# berlingo_synth.net
KiCad netlist of a schematic drawn in EAGLE
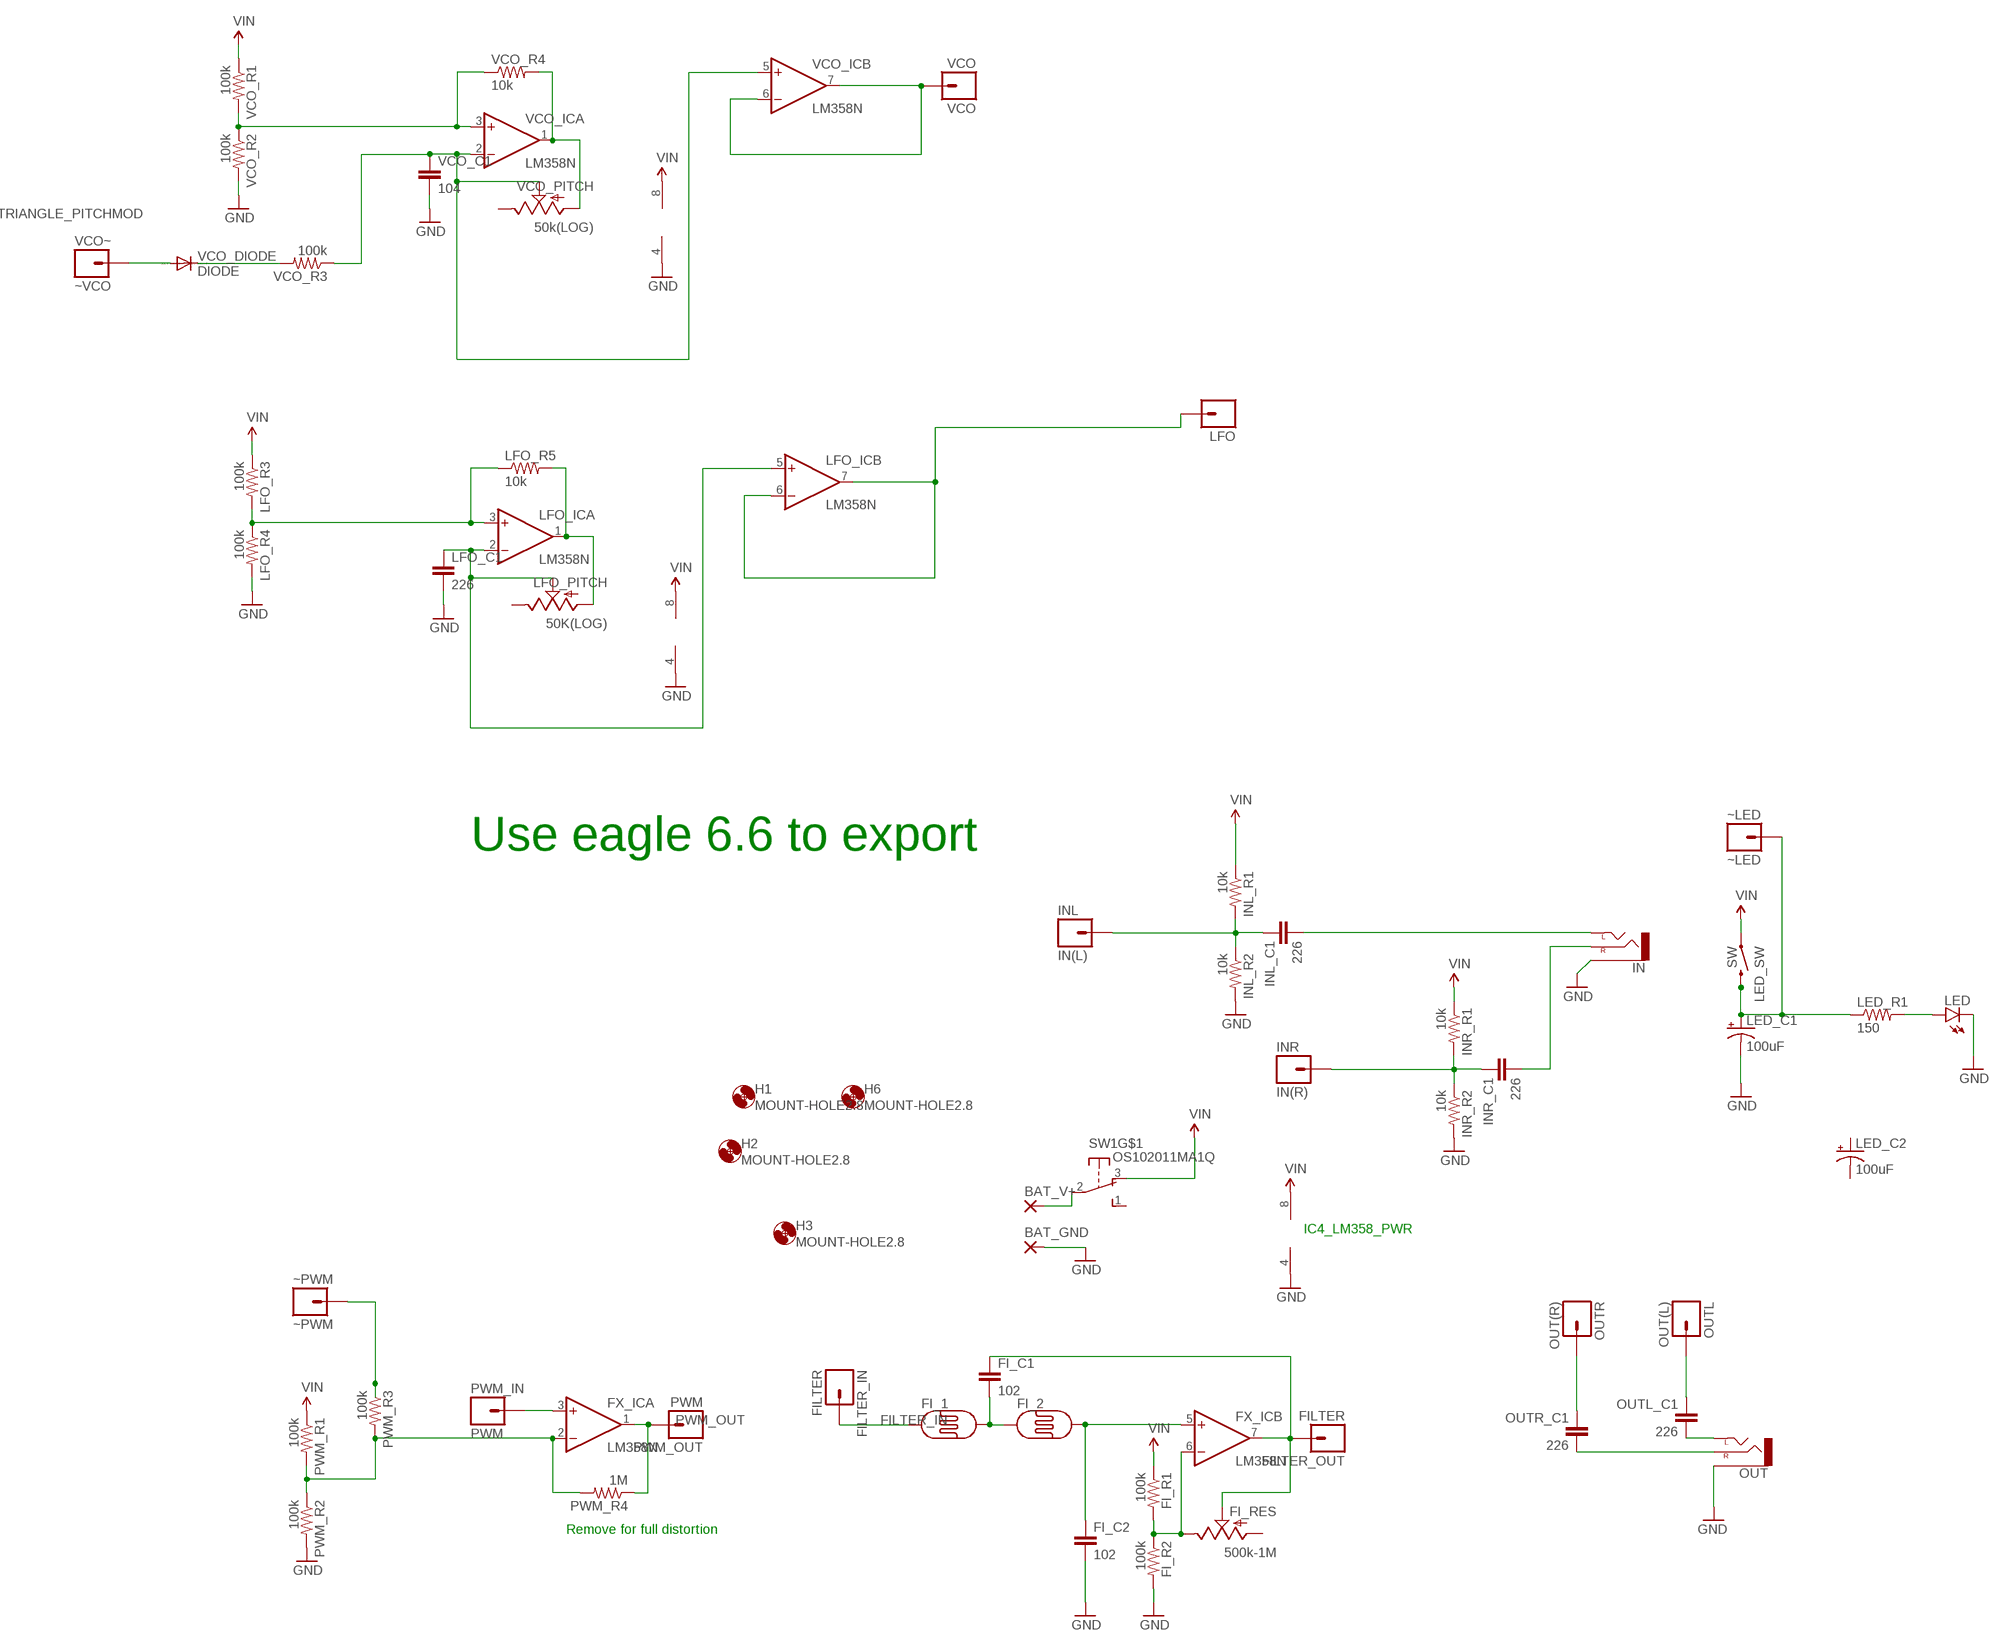
[diagram p0: schematic, sheet 1]

(export (version "E")
  (design (tool "Eeschema 10.0.6"))
  (components
    (comp (ref "BAT_GND")
      (value "3,81/1,4")
      (footprint "eagle-import:3,81_1,4")
      (libsource (lib "eagle-import") (part "3,81/1,4"))
    )
    (comp (ref "BAT_V+")
      (value "3,81/1,4")
      (footprint "eagle-import:3,81_1,4")
      (libsource (lib "eagle-import") (part "3,81/1,4"))
    )
    (comp (ref "FILTER_IN")
      (value "FILTER")
      (footprint "eagle-import:1X01_SIDE_NAME")
      (libsource (lib "eagle-import") (part "HEADER-1X1"))
    )
    (comp (ref "FILTER_OUT")
      (value "FILTER")
      (footprint "eagle-import:1X01_SIDE_NAME")
      (libsource (lib "eagle-import") (part "HEADER-1X1"))
    )
    (comp (ref "FI_1")
      (value "PHOTOCELLPTH")
      (footprint "eagle-import:PHOTOCELL")
      (libsource (lib "eagle-import") (part "PHOTOCELLPTH"))
    )
    (comp (ref "FI_2")
      (value "PHOTOCELLPTH")
      (footprint "eagle-import:PHOTOCELL")
      (libsource (lib "eagle-import") (part "PHOTOCELLPTH"))
    )
    (comp (ref "FI_C1")
      (value "102")
      (footprint "eagle-import:CAP-PTH-SMALLEZ")
      (libsource (lib "eagle-import") (part "CAPEZ"))
    )
    (comp (ref "FI_C2")
      (value "102")
      (footprint "eagle-import:CAP-PTH-SMALLEZ")
      (libsource (lib "eagle-import") (part "CAPEZ"))
    )
    (comp (ref "FI_R1")
      (value "100k")
      (footprint "eagle-import:0207_10")
      (libsource (lib "eagle-import") (part "R-US_0207/10"))
    )
    (comp (ref "FI_R2")
      (value "100k")
      (footprint "eagle-import:0207_10")
      (libsource (lib "eagle-import") (part "R-US_0207/10"))
    )
    (comp (ref "FI_RES")
      (value "500k-1M")
      (footprint "eagle-import:ALPS_POT")
      (libsource (lib "eagle-import") (part "POT"))
    )
    (comp (ref "FX_IC")
      (value "LM358N")
      (footprint "eagle-import:DIL08")
      (libsource (lib "eagle-import") (part "LM358N"))
    )
    (comp (ref "H1")
      (value "MOUNT-HOLE2.8")
      (footprint "eagle-import:2,8")
      (libsource (lib "eagle-import") (part "MOUNT-HOLE2.8"))
    )
    (comp (ref "H2")
      (value "MOUNT-HOLE2.8")
      (footprint "eagle-import:2,8")
      (libsource (lib "eagle-import") (part "MOUNT-HOLE2.8"))
    )
    (comp (ref "H3")
      (value "MOUNT-HOLE2.8")
      (footprint "eagle-import:2,8")
      (libsource (lib "eagle-import") (part "MOUNT-HOLE2.8"))
    )
    (comp (ref "H6")
      (value "MOUNT-HOLE2.8")
      (footprint "eagle-import:2,8")
      (libsource (lib "eagle-import") (part "MOUNT-HOLE2.8"))
    )
    (comp (ref "IN")
      (value "AUDIO-JACKPTH")
      (footprint "eagle-import:AUDIO-JACK")
      (libsource (lib "eagle-import") (part "AUDIO-JACKPTH"))
    )
    (comp (ref "INL")
      (value "IN(L)")
      (footprint "eagle-import:1X01_SIDE_NAME")
      (libsource (lib "eagle-import") (part "HEADER-1X1"))
    )
    (comp (ref "INL_C1")
      (value "226")
      (footprint "eagle-import:CAP-PTH-SMALLEZ")
      (libsource (lib "eagle-import") (part "CAPEZ"))
    )
    (comp (ref "INL_R1")
      (value "10k")
      (footprint "eagle-import:0207_10")
      (libsource (lib "eagle-import") (part "R-US_0207/10"))
    )
    (comp (ref "INL_R2")
      (value "10k")
      (footprint "eagle-import:0207_10")
      (libsource (lib "eagle-import") (part "R-US_0207/10"))
    )
    (comp (ref "INR")
      (value "IN(R)")
      (footprint "eagle-import:1X01_SIDE_NAME")
      (libsource (lib "eagle-import") (part "HEADER-1X1"))
    )
    (comp (ref "INR_C1")
      (value "226")
      (footprint "eagle-import:CAP-PTH-SMALLEZ")
      (libsource (lib "eagle-import") (part "CAPEZ"))
    )
    (comp (ref "INR_R1")
      (value "10k")
      (footprint "eagle-import:0207_10")
      (libsource (lib "eagle-import") (part "R-US_0207/10"))
    )
    (comp (ref "INR_R2")
      (value "10k")
      (footprint "eagle-import:0207_10")
      (libsource (lib "eagle-import") (part "R-US_0207/10"))
    )
    (comp (ref "LED")
      (value "LED5MM")
      (footprint "eagle-import:LED5MM")
      (libsource (lib "eagle-import") (part "LED5MM"))
    )
    (comp (ref "LED_C1")
      (value "100uF")
      (footprint "eagle-import:E2-4")
      (libsource (lib "eagle-import") (part "CPOL-USE2-4"))
    )
    (comp (ref "LED_C2")
      (value "100uF")
      (footprint "eagle-import:E2,5-6")
      (libsource (lib "eagle-import") (part "CPOL-USE2.5-6"))
    )
    (comp (ref "LED_R1")
      (value "150")
      (footprint "eagle-import:0207_10")
      (libsource (lib "eagle-import") (part "R-US_0207/10"))
    )
    (comp (ref "LED_SW")
      (value "SW")
      (footprint "eagle-import:TACTILE-PTH-12MM")
      (libsource (lib "eagle-import") (part "SWITCH-MOMENTARY-212MM"))
    )
    (comp (ref "LFO")
      (value "HEADER-1X1")
      (footprint "eagle-import:1X01_SIDE_NAME")
      (libsource (lib "eagle-import") (part "HEADER-1X1"))
    )
    (comp (ref "LFO_C1")
      (value "226")
      (footprint "eagle-import:CAP-PTH-SMALLEZ")
      (libsource (lib "eagle-import") (part "CAPEZ"))
    )
    (comp (ref "LFO_IC")
      (value "LM358N")
      (footprint "eagle-import:DIL08")
      (libsource (lib "eagle-import") (part "LM358N"))
    )
    (comp (ref "LFO_PITCH")
      (value "50K(LOG)")
      (footprint "eagle-import:ALPS_POT")
      (libsource (lib "eagle-import") (part "POT"))
    )
    (comp (ref "LFO_R3")
      (value "100k")
      (footprint "eagle-import:0207_10")
      (libsource (lib "eagle-import") (part "R-US_0207/10"))
    )
    (comp (ref "LFO_R4")
      (value "100k")
      (footprint "eagle-import:0207_10")
      (libsource (lib "eagle-import") (part "R-US_0207/10"))
    )
    (comp (ref "LFO_R5")
      (value "10k")
      (footprint "eagle-import:0207_10")
      (libsource (lib "eagle-import") (part "R-US_0207/10"))
    )
    (comp (ref "OUT")
      (value "AUDIO-JACKPTH")
      (footprint "eagle-import:AUDIO-JACK")
      (libsource (lib "eagle-import") (part "AUDIO-JACKPTH"))
    )
    (comp (ref "OUTL")
      (value "OUT(L)")
      (footprint "eagle-import:1X01_SIDE_NAME")
      (libsource (lib "eagle-import") (part "HEADER-1X1"))
    )
    (comp (ref "OUTL_C1")
      (value "226")
      (footprint "eagle-import:CAP-PTH-SMALLEZ")
      (libsource (lib "eagle-import") (part "CAPEZ"))
    )
    (comp (ref "OUTR")
      (value "OUT(R)")
      (footprint "eagle-import:1X01_SIDE_NAME")
      (libsource (lib "eagle-import") (part "HEADER-1X1"))
    )
    (comp (ref "OUTR_C1")
      (value "226")
      (footprint "eagle-import:CAP-PTH-SMALLEZ")
      (libsource (lib "eagle-import") (part "CAPEZ"))
    )
    (comp (ref "PWM_IN")
      (value "PWM")
      (footprint "eagle-import:1X01_SIDE_NAME")
      (libsource (lib "eagle-import") (part "HEADER-1X1"))
    )
    (comp (ref "PWM_OUT")
      (value "PWM")
      (footprint "eagle-import:1X01_SIDE_NAME")
      (libsource (lib "eagle-import") (part "HEADER-1X1"))
    )
    (comp (ref "PWM_R1")
      (value "100k")
      (footprint "eagle-import:0207_10")
      (libsource (lib "eagle-import") (part "R-US_0207/10"))
    )
    (comp (ref "PWM_R2")
      (value "100k")
      (footprint "eagle-import:0207_10")
      (libsource (lib "eagle-import") (part "R-US_0207/10"))
    )
    (comp (ref "PWM_R3")
      (value "100k")
      (footprint "eagle-import:0207_10")
      (libsource (lib "eagle-import") (part "R-US_0207/10"))
    )
    (comp (ref "PWM_R4")
      (value "1M")
      (footprint "eagle-import:0207_10")
      (libsource (lib "eagle-import") (part "R-US_0207/10"))
    )
    (comp (ref "SW1")
      (value "OS102011MA1Q")
      (footprint "eagle-import:OS102011MA1Q")
      (libsource (lib "eagle-import") (part "OS102011MA1Q"))
    )
    (comp (ref "VCO")
      (value "VCO")
      (footprint "eagle-import:1X01_SIDE_NAME")
      (libsource (lib "eagle-import") (part "HEADER-1X1"))
    )
    (comp (ref "VCO_C1")
      (value "104")
      (footprint "eagle-import:CAP-PTH-SMALLEZ")
      (libsource (lib "eagle-import") (part "CAPEZ"))
    )
    (comp (ref "VCO_DIODE")
      (value "DIODE")
      (footprint "eagle-import:DO41-10")
      (libsource (lib "eagle-import") (part "1N4004"))
    )
    (comp (ref "VCO_IC")
      (value "LM358N")
      (footprint "eagle-import:DIL08")
      (libsource (lib "eagle-import") (part "LM358N"))
    )
    (comp (ref "VCO_PITCH")
      (value "50k(LOG)")
      (footprint "eagle-import:ALPS_POT")
      (libsource (lib "eagle-import") (part "POT"))
    )
    (comp (ref "VCO_R1")
      (value "100k")
      (footprint "eagle-import:0207_10")
      (libsource (lib "eagle-import") (part "R-US_0207/10"))
    )
    (comp (ref "VCO_R2")
      (value "100k")
      (footprint "eagle-import:0207_10")
      (libsource (lib "eagle-import") (part "R-US_0207/10"))
    )
    (comp (ref "VCO_R3")
      (value "100k")
      (footprint "eagle-import:0207_10")
      (libsource (lib "eagle-import") (part "R-US_0207/10"))
    )
    (comp (ref "VCO_R4")
      (value "10k")
      (footprint "eagle-import:0207_10")
      (libsource (lib "eagle-import") (part "R-US_0207/10"))
    )
    (comp (ref "VCO~")
      (value "~VCO")
      (footprint "eagle-import:1X01_SIDE_NAME")
      (libsource (lib "eagle-import") (part "HEADER-1X1"))
    )
    (comp (ref "~LED")
      (value "~LED")
      (footprint "eagle-import:1X01_SIDE_NAME")
      (libsource (lib "eagle-import") (part "HEADER-1X1"))
    )
    (comp (ref "~PWM")
      (value "~PWM")
      (footprint "eagle-import:1X01_SIDE_NAME")
      (libsource (lib "eagle-import") (part "HEADER-1X1"))
    )
  )
  (nets
    (net (code "1") (name "/FILTER_IN") (class "Default")
      (node (ref "FILTER_IN") (pin "1") (pinfunction "1_1") (pintype "passive"))
      (node (ref "FI_1") (pin "1") (pinfunction "P$1_1") (pintype "bidirectional"))
    )
    (net (code "2") (name "/PWM_OUT") (class "Default")
      (node (ref "FX_IC") (pin "1") (pinfunction "OUT_1") (pintype "output"))
      (node (ref "PWM_OUT") (pin "1") (pinfunction "1_1") (pintype "passive"))
      (node (ref "PWM_R4") (pin "1") (pinfunction "1_1") (pintype "passive"))
    )
    (net (code "3") (name "/TRIANGLE_PITCHMOD") (class "Default")
      (node (ref "VCO_DIODE") (pin "A") (pinfunction "A_A") (pintype "passive"))
      (node (ref "VCO~") (pin "1") (pinfunction "1_1") (pintype "passive"))
    )
    (net (code "4") (name "GND") (class "Default")
      (node (ref "BAT_GND") (pin "1") (pinfunction "P_1") (pintype "passive"))
      (node (ref "FI_C2") (pin "2") (pinfunction "2_2") (pintype "passive"))
      (node (ref "FI_R2") (pin "2") (pinfunction "2_2") (pintype "passive"))
      (node (ref "FX_IC") (pin "4") (pinfunction "V-_4") (pintype "power_in"))
      (node (ref "IN") (pin "SLEEVE") (pinfunction "SLEEVE_SLEEVE") (pintype "bidirectional"))
      (node (ref "INL_R2") (pin "2") (pinfunction "2_2") (pintype "passive"))
      (node (ref "INR_R2") (pin "2") (pinfunction "2_2") (pintype "passive"))
      (node (ref "LED") (pin "K") (pinfunction "C_K") (pintype "passive"))
      (node (ref "LED_C1") (pin "-") (pinfunction "-_-") (pintype "passive"))
      (node (ref "LFO_C1") (pin "2") (pinfunction "2_2") (pintype "passive"))
      (node (ref "LFO_IC") (pin "4") (pinfunction "V-_4") (pintype "power_in"))
      (node (ref "LFO_R4") (pin "2") (pinfunction "2_2") (pintype "passive"))
      (node (ref "OUT") (pin "SLEEVE") (pinfunction "SLEEVE_SLEEVE") (pintype "bidirectional"))
      (node (ref "PWM_R2") (pin "2") (pinfunction "2_2") (pintype "passive"))
      (node (ref "VCO_C1") (pin "2") (pinfunction "2_2") (pintype "passive"))
      (node (ref "VCO_IC") (pin "4") (pinfunction "V-_4") (pintype "power_in"))
      (node (ref "VCO_R2") (pin "2") (pinfunction "2_2") (pintype "passive"))
    )
    (net (code "5") (name "Net-(BAT_V+-P)") (class "Default")
      (node (ref "BAT_V+") (pin "1") (pinfunction "P_1") (pintype "passive"))
      (node (ref "SW1") (pin "2") (pinfunction "P_2") (pintype "passive"))
    )
    (net (code "6") (name "Net-(FI_1-P$2)") (class "Default")
      (node (ref "FI_1") (pin "2") (pinfunction "P$2_2") (pintype "bidirectional"))
      (node (ref "FI_2") (pin "1") (pinfunction "P$1_1") (pintype "bidirectional"))
      (node (ref "FI_C1") (pin "2") (pinfunction "2_2") (pintype "passive"))
    )
    (net (code "7") (name "Net-(FI_2-P$2)") (class "Default")
      (node (ref "FI_2") (pin "2") (pinfunction "P$2_2") (pintype "bidirectional"))
      (node (ref "FI_C2") (pin "1") (pinfunction "1_1") (pintype "passive"))
      (node (ref "FX_IC") (pin "5") (pinfunction "+IN_5") (pintype "input"))
    )
    (net (code "8") (name "Net-(FI_RES-E)") (class "Default")
      (node (ref "FI_R1") (pin "2") (pinfunction "2_2") (pintype "passive"))
      (node (ref "FI_R2") (pin "1") (pinfunction "1_1") (pintype "passive"))
      (node (ref "FI_RES") (pin "P$1") (pinfunction "E_P$1") (pintype "passive"))
      (node (ref "FX_IC") (pin "6") (pinfunction "-IN_6") (pintype "input"))
    )
    (net (code "9") (name "Net-(FI_RES-S)") (class "Default")
      (node (ref "FILTER_OUT") (pin "1") (pinfunction "1_1") (pintype "passive"))
      (node (ref "FI_C1") (pin "1") (pinfunction "1_1") (pintype "passive"))
      (node (ref "FI_RES") (pin "P$2") (pinfunction "S_P$2") (pintype "passive"))
      (node (ref "FX_IC") (pin "7") (pinfunction "OUT_7") (pintype "output"))
    )
    (net (code "10") (name "Net-(FX_ICA-+IN)") (class "Default")
      (node (ref "FX_IC") (pin "3") (pinfunction "+IN_3") (pintype "input"))
      (node (ref "PWM_IN") (pin "1") (pinfunction "1_1") (pintype "passive"))
    )
    (net (code "11") (name "Net-(FX_ICA--IN)") (class "Default")
      (node (ref "FX_IC") (pin "2") (pinfunction "-IN_2") (pintype "input"))
      (node (ref "PWM_R1") (pin "2") (pinfunction "2_2") (pintype "passive"))
      (node (ref "PWM_R2") (pin "1") (pinfunction "1_1") (pintype "passive"))
      (node (ref "PWM_R3") (pin "2") (pinfunction "2_2") (pintype "passive"))
      (node (ref "PWM_R4") (pin "2") (pinfunction "2_2") (pintype "passive"))
    )
    (net (code "12") (name "Net-(IN-LEFT)") (class "Default")
      (node (ref "IN") (pin "TIP") (pinfunction "LEFT_TIP") (pintype "bidirectional"))
      (node (ref "INL_C1") (pin "2") (pinfunction "2_2") (pintype "passive"))
    )
    (net (code "13") (name "Net-(IN-RIGHT)") (class "Default")
      (node (ref "IN") (pin "RING") (pinfunction "RIGHT_RING") (pintype "bidirectional"))
      (node (ref "INR_C1") (pin "2") (pinfunction "2_2") (pintype "passive"))
    )
    (net (code "14") (name "Net-(INL-Pad1)") (class "Default")
      (node (ref "INL") (pin "1") (pinfunction "1_1") (pintype "passive"))
      (node (ref "INL_C1") (pin "1") (pinfunction "1_1") (pintype "passive"))
      (node (ref "INL_R1") (pin "2") (pinfunction "2_2") (pintype "passive"))
      (node (ref "INL_R2") (pin "1") (pinfunction "1_1") (pintype "passive"))
    )
    (net (code "15") (name "Net-(INR-Pad1)") (class "Default")
      (node (ref "INR") (pin "1") (pinfunction "1_1") (pintype "passive"))
      (node (ref "INR_C1") (pin "1") (pinfunction "1_1") (pintype "passive"))
      (node (ref "INR_R1") (pin "2") (pinfunction "2_2") (pintype "passive"))
      (node (ref "INR_R2") (pin "1") (pinfunction "1_1") (pintype "passive"))
    )
    (net (code "16") (name "Net-(LED-PadA)") (class "Default")
      (node (ref "LED") (pin "A") (pinfunction "A_A") (pintype "passive"))
      (node (ref "LED_R1") (pin "2") (pinfunction "2_2") (pintype "passive"))
    )
    (net (code "17") (name "Net-(LED_SW-2)") (class "Default")
      (node (ref "LED_C1") (pin "+") (pinfunction "+_+") (pintype "passive"))
      (node (ref "LED_R1") (pin "1") (pinfunction "1_1") (pintype "passive"))
      (node (ref "LED_SW") (pin "3") (pinfunction "2_3") (pintype "passive"))
      (node (ref "~LED") (pin "1") (pinfunction "1_1") (pintype "passive"))
    )
    (net (code "18") (name "Net-(LFO_ICA-+IN)") (class "Default")
      (node (ref "LFO_IC") (pin "3") (pinfunction "+IN_3") (pintype "input"))
      (node (ref "LFO_R3") (pin "2") (pinfunction "2_2") (pintype "passive"))
      (node (ref "LFO_R4") (pin "1") (pinfunction "1_1") (pintype "passive"))
      (node (ref "LFO_R5") (pin "1") (pinfunction "1_1") (pintype "passive"))
    )
    (net (code "19") (name "Net-(LFO_ICA--IN)") (class "Default")
      (node (ref "LFO_C1") (pin "1") (pinfunction "1_1") (pintype "passive"))
      (node (ref "LFO_IC") (pin "2") (pinfunction "-IN_2") (pintype "input"))
      (node (ref "LFO_IC") (pin "5") (pinfunction "+IN_5") (pintype "input"))
      (node (ref "LFO_PITCH") (pin "P$2") (pinfunction "S_P$2") (pintype "passive"))
    )
    (net (code "20") (name "Net-(LFO_ICA-OUT)") (class "Default")
      (node (ref "LFO_IC") (pin "1") (pinfunction "OUT_1") (pintype "output"))
      (node (ref "LFO_PITCH") (pin "P$3") (pinfunction "A_P$3") (pintype "passive"))
      (node (ref "LFO_R5") (pin "2") (pinfunction "2_2") (pintype "passive"))
    )
    (net (code "21") (name "Net-(LFO_ICB--IN)") (class "Default")
      (node (ref "LFO") (pin "1") (pinfunction "1_1") (pintype "passive"))
      (node (ref "LFO_IC") (pin "6") (pinfunction "-IN_6") (pintype "input"))
      (node (ref "LFO_IC") (pin "7") (pinfunction "OUT_7") (pintype "output"))
    )
    (net (code "22") (name "Net-(OUT-LEFT)") (class "Default")
      (node (ref "OUT") (pin "TIP") (pinfunction "LEFT_TIP") (pintype "bidirectional"))
      (node (ref "OUTL_C1") (pin "2") (pinfunction "2_2") (pintype "passive"))
    )
    (net (code "23") (name "Net-(OUT-RIGHT)") (class "Default")
      (node (ref "OUT") (pin "RING") (pinfunction "RIGHT_RING") (pintype "bidirectional"))
      (node (ref "OUTR_C1") (pin "2") (pinfunction "2_2") (pintype "passive"))
    )
    (net (code "24") (name "Net-(OUTL-Pad1)") (class "Default")
      (node (ref "OUTL") (pin "1") (pinfunction "1_1") (pintype "passive"))
      (node (ref "OUTL_C1") (pin "1") (pinfunction "1_1") (pintype "passive"))
    )
    (net (code "25") (name "Net-(OUTR-Pad1)") (class "Default")
      (node (ref "OUTR") (pin "1") (pinfunction "1_1") (pintype "passive"))
      (node (ref "OUTR_C1") (pin "1") (pinfunction "1_1") (pintype "passive"))
    )
    (net (code "26") (name "Net-(PWM_R3-Pad1)") (class "Default")
      (node (ref "PWM_R3") (pin "1") (pinfunction "1_1") (pintype "passive"))
      (node (ref "~PWM") (pin "1") (pinfunction "1_1") (pintype "passive"))
    )
    (net (code "27") (name "Net-(VCO_DIODE-PadC)") (class "Default")
      (node (ref "VCO_DIODE") (pin "C") (pinfunction "C_C") (pintype "passive"))
      (node (ref "VCO_R3") (pin "2") (pinfunction "2_2") (pintype "passive"))
    )
    (net (code "28") (name "Net-(VCO_ICA-+IN)") (class "Default")
      (node (ref "VCO_IC") (pin "3") (pinfunction "+IN_3") (pintype "input"))
      (node (ref "VCO_R1") (pin "2") (pinfunction "2_2") (pintype "passive"))
      (node (ref "VCO_R2") (pin "1") (pinfunction "1_1") (pintype "passive"))
      (node (ref "VCO_R4") (pin "1") (pinfunction "1_1") (pintype "passive"))
    )
    (net (code "29") (name "Net-(VCO_ICA--IN)") (class "Default")
      (node (ref "VCO_C1") (pin "1") (pinfunction "1_1") (pintype "passive"))
      (node (ref "VCO_IC") (pin "2") (pinfunction "-IN_2") (pintype "input"))
      (node (ref "VCO_IC") (pin "5") (pinfunction "+IN_5") (pintype "input"))
      (node (ref "VCO_PITCH") (pin "P$2") (pinfunction "S_P$2") (pintype "passive"))
      (node (ref "VCO_R3") (pin "1") (pinfunction "1_1") (pintype "passive"))
    )
    (net (code "30") (name "Net-(VCO_ICA-OUT)") (class "Default")
      (node (ref "VCO_IC") (pin "1") (pinfunction "OUT_1") (pintype "output"))
      (node (ref "VCO_PITCH") (pin "P$3") (pinfunction "A_P$3") (pintype "passive"))
      (node (ref "VCO_R4") (pin "2") (pinfunction "2_2") (pintype "passive"))
    )
    (net (code "31") (name "Net-(VCO_ICB--IN)") (class "Default")
      (node (ref "VCO") (pin "1") (pinfunction "1_1") (pintype "passive"))
      (node (ref "VCO_IC") (pin "6") (pinfunction "-IN_6") (pintype "input"))
      (node (ref "VCO_IC") (pin "7") (pinfunction "OUT_7") (pintype "output"))
    )
    (net (code "32") (name "VIN") (class "Default")
      (node (ref "FI_R1") (pin "1") (pinfunction "1_1") (pintype "passive"))
      (node (ref "FX_IC") (pin "8") (pinfunction "V+_8") (pintype "power_in"))
      (node (ref "INL_R1") (pin "1") (pinfunction "1_1") (pintype "passive"))
      (node (ref "INR_R1") (pin "1") (pinfunction "1_1") (pintype "passive"))
      (node (ref "LED_SW") (pin "1") (pinfunction "1_1") (pintype "passive"))
      (node (ref "LFO_IC") (pin "8") (pinfunction "V+_8") (pintype "power_in"))
      (node (ref "LFO_R3") (pin "1") (pinfunction "1_1") (pintype "passive"))
      (node (ref "PWM_R1") (pin "1") (pinfunction "1_1") (pintype "passive"))
      (node (ref "SW1") (pin "3") (pinfunction "O_3") (pintype "passive"))
      (node (ref "VCO_IC") (pin "8") (pinfunction "V+_8") (pintype "power_in"))
      (node (ref "VCO_R1") (pin "1") (pinfunction "1_1") (pintype "passive"))
    )
    (net (code "33") (name "unconnected-(FI_RES-A-PadP$3)") (class "Default")
      (node (ref "FI_RES") (pin "P$3") (pinfunction "A_P$3") (pintype "passive"))
    )
    (net (code "34") (name "unconnected-(LED_C2-Pad+)") (class "Default")
      (node (ref "LED_C2") (pin "+") (pinfunction "+_+") (pintype "passive"))
    )
    (net (code "35") (name "unconnected-(LED_C2-Pad-)") (class "Default")
      (node (ref "LED_C2") (pin "-") (pinfunction "-_-") (pintype "passive"))
    )
    (net (code "36") (name "unconnected-(LFO_PITCH-E-PadP$1)") (class "Default")
      (node (ref "LFO_PITCH") (pin "P$1") (pinfunction "E_P$1") (pintype "passive"))
    )
    (net (code "37") (name "unconnected-(SW1A-S-Pad1)") (class "Default")
      (node (ref "SW1") (pin "1") (pinfunction "S_1") (pintype "passive"))
    )
    (net (code "38") (name "unconnected-(VCO_PITCH-E-PadP$1)") (class "Default")
      (node (ref "VCO_PITCH") (pin "P$1") (pinfunction "E_P$1") (pintype "passive"))
    )
  )
)
